# Sch_MB.net
KiCad netlist of a schematic drawn in Altium Designer
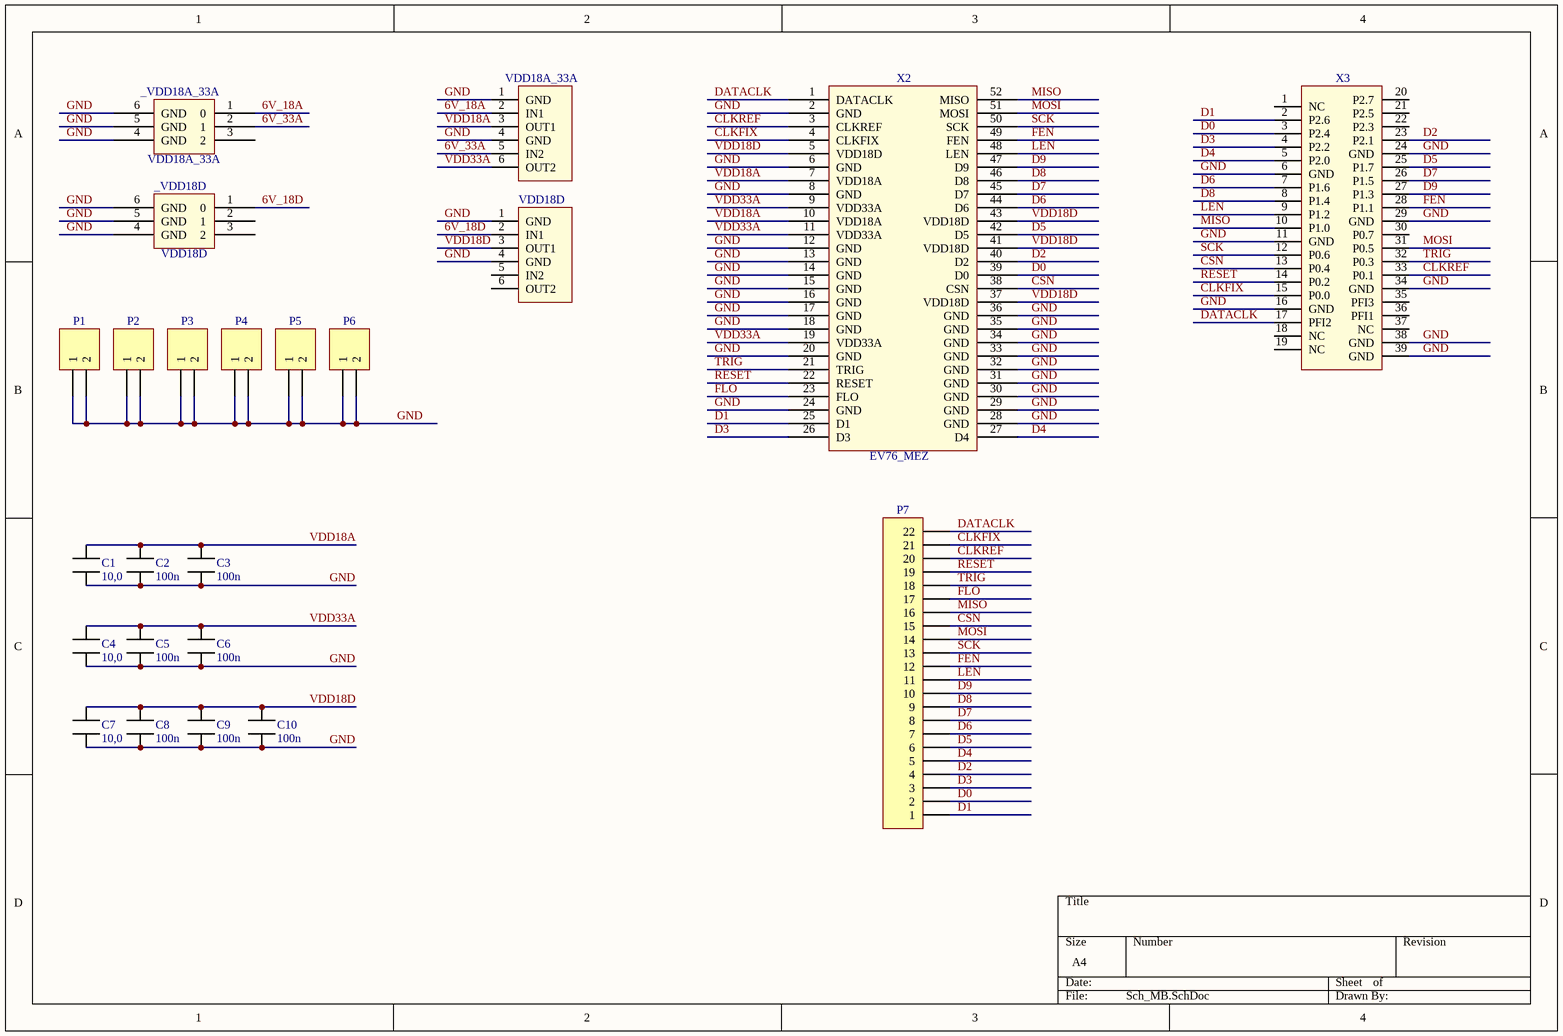
[diagram p0: Sch_MB.SchDoc]

(export (version "E")
  (design (tool "Eeschema 10.0.6"))
  (components
    (comp (ref "C1") (value "10,0") (footprint "Cap_BIG") (libsource (lib "Schlib") (part "CAP_BIG")))
    (comp (ref "C2") (value "100n") (footprint "CAP_SMALL") (libsource (lib "Schlib") (part "CAP_SMALL")))
    (comp (ref "C3") (value "100n") (footprint "CAP_SMALL") (libsource (lib "Schlib") (part "CAP_SMALL")))
    (comp (ref "C4") (value "10,0") (footprint "Cap_BIG") (libsource (lib "Schlib") (part "CAP_BIG")))
    (comp (ref "C5") (value "100n") (footprint "CAP_SMALL") (libsource (lib "Schlib") (part "CAP_SMALL")))
    (comp (ref "C6") (value "100n") (footprint "CAP_SMALL") (libsource (lib "Schlib") (part "CAP_SMALL")))
    (comp (ref "C7") (value "10,0") (footprint "Cap_BIG") (libsource (lib "Schlib") (part "CAP_BIG")))
    (comp (ref "C8") (value "100n") (footprint "CAP_SMALL") (libsource (lib "Schlib") (part "CAP_SMALL")))
    (comp (ref "C9") (value "100n") (footprint "CAP_SMALL") (libsource (lib "Schlib") (part "CAP_SMALL")))
    (comp (ref "C10") (value "100n") (footprint "CAP_SMALL") (libsource (lib "Schlib") (part "CAP_SMALL")))
    (comp (ref "P1")
      (value "Header 2")
      (footprint "HDR1X2")
      (description "Header, 2-Pin")
      (fields (field (name "PUBLISHER") "Altium Limited"))
      (libsource (lib "Miscellaneous Connectors") (part "Header 2"))
    )
    (comp (ref "P2")
      (value "Header 2")
      (footprint "HDR1X2")
      (description "Header, 2-Pin")
      (fields (field (name "PUBLISHER") "Altium Limited"))
      (libsource (lib "Miscellaneous Connectors") (part "Header 2"))
    )
    (comp (ref "P3")
      (value "Header 2")
      (footprint "HDR1X2")
      (description "Header, 2-Pin")
      (fields (field (name "PUBLISHER") "Altium Limited"))
      (libsource (lib "Miscellaneous Connectors") (part "Header 2"))
    )
    (comp (ref "P4")
      (value "Header 2")
      (footprint "HDR1X2")
      (description "Header, 2-Pin")
      (fields (field (name "PUBLISHER") "Altium Limited"))
      (libsource (lib "Miscellaneous Connectors") (part "Header 2"))
    )
    (comp (ref "P5")
      (value "Header 2")
      (footprint "HDR1X2")
      (description "Header, 2-Pin")
      (fields (field (name "PUBLISHER") "Altium Limited"))
      (libsource (lib "Miscellaneous Connectors") (part "Header 2"))
    )
    (comp (ref "P6")
      (value "Header 2")
      (footprint "HDR1X2")
      (description "Header, 2-Pin")
      (fields (field (name "PUBLISHER") "Altium Limited"))
      (libsource (lib "Miscellaneous Connectors") (part "Header 2"))
    )
    (comp (ref "P7")
      (value "Header 22")
      (footprint "HDR1X22")
      (description "Header, 22-Pin")
      (fields (field (name "PUBLISHER") "Altium Limited"))
      (libsource (lib "Miscellaneous Connectors") (part "Header 22"))
    )
    (comp (ref "VDD18A_33A")
      (value "VDD18A_33A")
      (footprint "MEZON_POWER_NEW")
      (libsource (lib "Schlib") (part "MEZON_POWER_NEW"))
    )
    (comp (ref "VDD18D")
      (value "VDD18D")
      (footprint "MEZON_POWER_NEW")
      (libsource (lib "Schlib") (part "MEZON_POWER_NEW"))
    )
    (comp (ref "X2")
      (value "EV76_MEZ")
      (footprint "EV76C661_MEZONINE")
      (libsource (lib "Schlib") (part "EV76C661_MEZ"))
    )
    (comp (ref "X3")
      (value "CHEAP_CON_37_FEMALE")
      (footprint "CHEAP_CONN_FEMALE")
      (libsource (lib "Schlib") (part "CHEAP_CON_37_FEMALE"))
    )
    (comp (ref "_VDD18A_33A")
      (value "VDD18A_33A")
      (footprint "POWER")
      (libsource (lib "Schlib") (part "POWER"))
    )
    (comp (ref "_VDD18D") (value "VDD18D") (footprint "POWER") (libsource (lib "Schlib") (part "POWER")))
  )
  (nets
    (net (code "1") (name "/6V_18A") (class "Default")
      (node (ref "VDD18A_33A") (pin "2") (pinfunction "IN1_2") (pintype "passive"))
      (node (ref "_VDD18A_33A") (pin "1") (pinfunction "0_1") (pintype "passive"))
    )
    (net (code "2") (name "/6V_18D") (class "Default")
      (node (ref "VDD18D") (pin "2") (pinfunction "IN1_2") (pintype "passive"))
      (node (ref "_VDD18D") (pin "1") (pinfunction "0_1") (pintype "passive"))
    )
    (net (code "3") (name "/6V_33A") (class "Default")
      (node (ref "VDD18A_33A") (pin "5") (pinfunction "IN2_5") (pintype "passive"))
      (node (ref "_VDD18A_33A") (pin "2") (pinfunction "1_2") (pintype "passive"))
    )
    (net (code "4") (name "/CLKFIX") (class "Default")
      (node (ref "P7") (pin "21") (pinfunction "21_21") (pintype "passive"))
      (node (ref "X2") (pin "4") (pinfunction "CLKFIX_4") (pintype "passive"))
      (node (ref "X3") (pin "15") (pinfunction "P0.0_15") (pintype "passive"))
    )
    (net (code "5") (name "/CLKREF") (class "Default")
      (node (ref "P7") (pin "20") (pinfunction "20_20") (pintype "passive"))
      (node (ref "X2") (pin "3") (pinfunction "CLKREF_3") (pintype "passive"))
      (node (ref "X3") (pin "33") (pinfunction "P0.1_33") (pintype "passive"))
    )
    (net (code "6") (name "/CSN") (class "Default")
      (node (ref "P7") (pin "15") (pinfunction "15_15") (pintype "passive"))
      (node (ref "X2") (pin "38") (pinfunction "CSN_38") (pintype "passive"))
      (node (ref "X3") (pin "13") (pinfunction "P0.4_13") (pintype "passive"))
    )
    (net (code "7") (name "/D0") (class "Default")
      (node (ref "P7") (pin "2") (pinfunction "2_2") (pintype "passive"))
      (node (ref "X2") (pin "39") (pinfunction "D0_39") (pintype "passive"))
      (node (ref "X3") (pin "3") (pinfunction "P2.4_3") (pintype "passive"))
    )
    (net (code "8") (name "/D1") (class "Default")
      (node (ref "P7") (pin "1") (pinfunction "1_1") (pintype "passive"))
      (node (ref "X2") (pin "25") (pinfunction "D1_25") (pintype "passive"))
      (node (ref "X3") (pin "2") (pinfunction "P2.6_2") (pintype "passive"))
    )
    (net (code "9") (name "/D2") (class "Default")
      (node (ref "P7") (pin "4") (pinfunction "4_4") (pintype "passive"))
      (node (ref "X2") (pin "40") (pinfunction "D2_40") (pintype "passive"))
      (node (ref "X3") (pin "23") (pinfunction "P2.1_23") (pintype "passive"))
    )
    (net (code "10") (name "/D3") (class "Default")
      (node (ref "P7") (pin "3") (pinfunction "3_3") (pintype "passive"))
      (node (ref "X2") (pin "26") (pinfunction "D3_26") (pintype "passive"))
      (node (ref "X3") (pin "4") (pinfunction "P2.2_4") (pintype "passive"))
    )
    (net (code "11") (name "/D4") (class "Default")
      (node (ref "P7") (pin "5") (pinfunction "5_5") (pintype "passive"))
      (node (ref "X2") (pin "27") (pinfunction "D4_27") (pintype "passive"))
      (node (ref "X3") (pin "5") (pinfunction "P2.0_5") (pintype "passive"))
    )
    (net (code "12") (name "/D5") (class "Default")
      (node (ref "P7") (pin "6") (pinfunction "6_6") (pintype "passive"))
      (node (ref "X2") (pin "42") (pinfunction "D5_42") (pintype "passive"))
      (node (ref "X3") (pin "25") (pinfunction "P1.7_25") (pintype "passive"))
    )
    (net (code "13") (name "/D6") (class "Default")
      (node (ref "P7") (pin "7") (pinfunction "7_7") (pintype "passive"))
      (node (ref "X2") (pin "44") (pinfunction "D6_44") (pintype "passive"))
      (node (ref "X3") (pin "7") (pinfunction "P1.6_7") (pintype "passive"))
    )
    (net (code "14") (name "/D7") (class "Default")
      (node (ref "P7") (pin "8") (pinfunction "8_8") (pintype "passive"))
      (node (ref "X2") (pin "45") (pinfunction "D7_45") (pintype "passive"))
      (node (ref "X3") (pin "26") (pinfunction "P1.5_26") (pintype "passive"))
    )
    (net (code "15") (name "/D8") (class "Default")
      (node (ref "P7") (pin "9") (pinfunction "9_9") (pintype "passive"))
      (node (ref "X2") (pin "46") (pinfunction "D8_46") (pintype "passive"))
      (node (ref "X3") (pin "8") (pinfunction "P1.4_8") (pintype "passive"))
    )
    (net (code "16") (name "/D9") (class "Default")
      (node (ref "P7") (pin "10") (pinfunction "10_10") (pintype "passive"))
      (node (ref "X2") (pin "47") (pinfunction "D9_47") (pintype "passive"))
      (node (ref "X3") (pin "27") (pinfunction "P1.3_27") (pintype "passive"))
    )
    (net (code "17") (name "/DATACLK") (class "Default")
      (node (ref "P7") (pin "22") (pinfunction "22_22") (pintype "passive"))
      (node (ref "X2") (pin "1") (pinfunction "DATACLK_1") (pintype "passive"))
      (node (ref "X3") (pin "17") (pinfunction "PFI2_17") (pintype "passive"))
    )
    (net (code "18") (name "/FEN") (class "Default")
      (node (ref "P7") (pin "12") (pinfunction "12_12") (pintype "passive"))
      (node (ref "X2") (pin "49") (pinfunction "FEN_49") (pintype "passive"))
      (node (ref "X3") (pin "28") (pinfunction "P1.1_28") (pintype "passive"))
    )
    (net (code "19") (name "/FLO") (class "Default")
      (node (ref "P7") (pin "17") (pinfunction "17_17") (pintype "passive"))
      (node (ref "X2") (pin "23") (pinfunction "FLO_23") (pintype "passive"))
    )
    (net (code "20") (name "/GND") (class "Default")
      (node (ref "C1") (pin "1") (pinfunction "1_1") (pintype "passive"))
      (node (ref "C10") (pin "1") (pinfunction "1_1") (pintype "passive"))
      (node (ref "C2") (pin "1") (pinfunction "1_1") (pintype "passive"))
      (node (ref "C3") (pin "1") (pinfunction "1_1") (pintype "passive"))
      (node (ref "C4") (pin "1") (pinfunction "1_1") (pintype "passive"))
      (node (ref "C5") (pin "1") (pinfunction "1_1") (pintype "passive"))
      (node (ref "C6") (pin "1") (pinfunction "1_1") (pintype "passive"))
      (node (ref "C7") (pin "1") (pinfunction "1_1") (pintype "passive"))
      (node (ref "C8") (pin "1") (pinfunction "1_1") (pintype "passive"))
      (node (ref "C9") (pin "1") (pinfunction "1_1") (pintype "passive"))
      (node (ref "P1") (pin "1") (pinfunction "1_1") (pintype "passive"))
      (node (ref "P1") (pin "2") (pinfunction "2_2") (pintype "passive"))
      (node (ref "P2") (pin "1") (pinfunction "1_1") (pintype "passive"))
      (node (ref "P2") (pin "2") (pinfunction "2_2") (pintype "passive"))
      (node (ref "P3") (pin "1") (pinfunction "1_1") (pintype "passive"))
      (node (ref "P3") (pin "2") (pinfunction "2_2") (pintype "passive"))
      (node (ref "P4") (pin "1") (pinfunction "1_1") (pintype "passive"))
      (node (ref "P4") (pin "2") (pinfunction "2_2") (pintype "passive"))
      (node (ref "P5") (pin "1") (pinfunction "1_1") (pintype "passive"))
      (node (ref "P5") (pin "2") (pinfunction "2_2") (pintype "passive"))
      (node (ref "P6") (pin "1") (pinfunction "1_1") (pintype "passive"))
      (node (ref "P6") (pin "2") (pinfunction "2_2") (pintype "passive"))
      (node (ref "VDD18A_33A") (pin "1") (pinfunction "GND_1") (pintype "passive"))
      (node (ref "VDD18A_33A") (pin "4") (pinfunction "GND_4") (pintype "passive"))
      (node (ref "VDD18D") (pin "1") (pinfunction "GND_1") (pintype "passive"))
      (node (ref "VDD18D") (pin "4") (pinfunction "GND_4") (pintype "passive"))
      (node (ref "X2") (pin "12") (pinfunction "GND_12") (pintype "passive"))
      (node (ref "X2") (pin "13") (pinfunction "GND_13") (pintype "passive"))
      (node (ref "X2") (pin "14") (pinfunction "GND_14") (pintype "passive"))
      (node (ref "X2") (pin "15") (pinfunction "GND_15") (pintype "passive"))
      (node (ref "X2") (pin "16") (pinfunction "GND_16") (pintype "passive"))
      (node (ref "X2") (pin "17") (pinfunction "GND_17") (pintype "passive"))
      (node (ref "X2") (pin "18") (pinfunction "GND_18") (pintype "passive"))
      (node (ref "X2") (pin "2") (pinfunction "GND_2") (pintype "passive"))
      (node (ref "X2") (pin "20") (pinfunction "GND_20") (pintype "passive"))
      (node (ref "X2") (pin "24") (pinfunction "GND_24") (pintype "passive"))
      (node (ref "X2") (pin "28") (pinfunction "GND_28") (pintype "passive"))
      (node (ref "X2") (pin "29") (pinfunction "GND_29") (pintype "passive"))
      (node (ref "X2") (pin "30") (pinfunction "GND_30") (pintype "passive"))
      (node (ref "X2") (pin "31") (pinfunction "GND_31") (pintype "passive"))
      (node (ref "X2") (pin "32") (pinfunction "GND_32") (pintype "passive"))
      (node (ref "X2") (pin "33") (pinfunction "GND_33") (pintype "passive"))
      (node (ref "X2") (pin "34") (pinfunction "GND_34") (pintype "passive"))
      (node (ref "X2") (pin "35") (pinfunction "GND_35") (pintype "passive"))
      (node (ref "X2") (pin "36") (pinfunction "GND_36") (pintype "passive"))
      (node (ref "X2") (pin "6") (pinfunction "GND_6") (pintype "passive"))
      (node (ref "X2") (pin "8") (pinfunction "GND_8") (pintype "passive"))
      (node (ref "X3") (pin "11") (pinfunction "GND_11") (pintype "passive"))
      (node (ref "X3") (pin "16") (pinfunction "GND_16") (pintype "passive"))
      (node (ref "X3") (pin "24") (pinfunction "GND_24") (pintype "passive"))
      (node (ref "X3") (pin "29") (pinfunction "GND_29") (pintype "passive"))
      (node (ref "X3") (pin "34") (pinfunction "GND_34") (pintype "passive"))
      (node (ref "X3") (pin "38") (pinfunction "GND_38") (pintype "passive"))
      (node (ref "X3") (pin "39") (pinfunction "GND_39") (pintype "passive"))
      (node (ref "X3") (pin "6") (pinfunction "GND_6") (pintype "passive"))
      (node (ref "_VDD18A_33A") (pin "4") (pinfunction "GND_4") (pintype "passive"))
      (node (ref "_VDD18A_33A") (pin "5") (pinfunction "GND_5") (pintype "passive"))
      (node (ref "_VDD18A_33A") (pin "6") (pinfunction "GND_6") (pintype "passive"))
      (node (ref "_VDD18D") (pin "4") (pinfunction "GND_4") (pintype "passive"))
      (node (ref "_VDD18D") (pin "5") (pinfunction "GND_5") (pintype "passive"))
      (node (ref "_VDD18D") (pin "6") (pinfunction "GND_6") (pintype "passive"))
    )
    (net (code "21") (name "/LEN") (class "Default")
      (node (ref "P7") (pin "11") (pinfunction "11_11") (pintype "passive"))
      (node (ref "X2") (pin "48") (pinfunction "LEN_48") (pintype "passive"))
      (node (ref "X3") (pin "9") (pinfunction "P1.2_9") (pintype "passive"))
    )
    (net (code "22") (name "/MISO") (class "Default")
      (node (ref "P7") (pin "16") (pinfunction "16_16") (pintype "passive"))
      (node (ref "X2") (pin "52") (pinfunction "MISO_52") (pintype "passive"))
      (node (ref "X3") (pin "10") (pinfunction "P1.0_10") (pintype "passive"))
    )
    (net (code "23") (name "/MOSI") (class "Default")
      (node (ref "P7") (pin "14") (pinfunction "14_14") (pintype "passive"))
      (node (ref "X2") (pin "51") (pinfunction "MOSI_51") (pintype "passive"))
      (node (ref "X3") (pin "31") (pinfunction "P0.5_31") (pintype "passive"))
    )
    (net (code "24") (name "/RESET") (class "Default")
      (node (ref "P7") (pin "19") (pinfunction "19_19") (pintype "passive"))
      (node (ref "X2") (pin "22") (pinfunction "RESET_22") (pintype "passive"))
      (node (ref "X3") (pin "14") (pinfunction "P0.2_14") (pintype "passive"))
    )
    (net (code "25") (name "/SCK") (class "Default")
      (node (ref "P7") (pin "13") (pinfunction "13_13") (pintype "passive"))
      (node (ref "X2") (pin "50") (pinfunction "SCK_50") (pintype "passive"))
      (node (ref "X3") (pin "12") (pinfunction "P0.6_12") (pintype "passive"))
    )
    (net (code "26") (name "/TRIG") (class "Default")
      (node (ref "P7") (pin "18") (pinfunction "18_18") (pintype "passive"))
      (node (ref "X2") (pin "21") (pinfunction "TRIG_21") (pintype "passive"))
      (node (ref "X3") (pin "32") (pinfunction "P0.3_32") (pintype "passive"))
    )
    (net (code "27") (name "/VDD18A") (class "Default")
      (node (ref "C1") (pin "2") (pinfunction "2_2") (pintype "passive"))
      (node (ref "C2") (pin "2") (pinfunction "2_2") (pintype "passive"))
      (node (ref "C3") (pin "2") (pinfunction "2_2") (pintype "passive"))
      (node (ref "VDD18A_33A") (pin "3") (pinfunction "OUT1_3") (pintype "passive"))
      (node (ref "X2") (pin "10") (pinfunction "VDD18A_10") (pintype "passive"))
      (node (ref "X2") (pin "7") (pinfunction "VDD18A_7") (pintype "passive"))
    )
    (net (code "28") (name "/VDD18D") (class "Default")
      (node (ref "C10") (pin "2") (pinfunction "2_2") (pintype "passive"))
      (node (ref "C7") (pin "2") (pinfunction "2_2") (pintype "passive"))
      (node (ref "C8") (pin "2") (pinfunction "2_2") (pintype "passive"))
      (node (ref "C9") (pin "2") (pinfunction "2_2") (pintype "passive"))
      (node (ref "VDD18D") (pin "3") (pinfunction "OUT1_3") (pintype "passive"))
      (node (ref "X2") (pin "37") (pinfunction "VDD18D_37") (pintype "passive"))
      (node (ref "X2") (pin "41") (pinfunction "VDD18D_41") (pintype "passive"))
      (node (ref "X2") (pin "43") (pinfunction "VDD18D_43") (pintype "passive"))
      (node (ref "X2") (pin "5") (pinfunction "VDD18D_5") (pintype "passive"))
    )
    (net (code "29") (name "/VDD33A") (class "Default")
      (node (ref "C4") (pin "2") (pinfunction "2_2") (pintype "passive"))
      (node (ref "C5") (pin "2") (pinfunction "2_2") (pintype "passive"))
      (node (ref "C6") (pin "2") (pinfunction "2_2") (pintype "passive"))
      (node (ref "VDD18A_33A") (pin "6") (pinfunction "OUT2_6") (pintype "passive"))
      (node (ref "X2") (pin "11") (pinfunction "VDD33A_11") (pintype "passive"))
      (node (ref "X2") (pin "19") (pinfunction "VDD33A_19") (pintype "passive"))
      (node (ref "X2") (pin "9") (pinfunction "VDD33A_9") (pintype "passive"))
    )
    (net (code "30") (name "unconnected-(VDD18D-IN2-Pad5)") (class "Default")
      (node (ref "VDD18D") (pin "5") (pinfunction "IN2_5") (pintype "passive"))
    )
    (net (code "31") (name "unconnected-(VDD18D-OUT2-Pad6)") (class "Default")
      (node (ref "VDD18D") (pin "6") (pinfunction "OUT2_6") (pintype "passive"))
    )
    (net (code "32") (name "unconnected-(X3-NC-Pad1)") (class "Default")
      (node (ref "X3") (pin "1") (pinfunction "NC_1") (pintype "passive"))
    )
    (net (code "33") (name "unconnected-(X3-NC-Pad18)") (class "Default")
      (node (ref "X3") (pin "18") (pinfunction "NC_18") (pintype "passive"))
    )
    (net (code "34") (name "unconnected-(X3-NC-Pad19)") (class "Default")
      (node (ref "X3") (pin "19") (pinfunction "NC_19") (pintype "passive"))
    )
    (net (code "35") (name "unconnected-(X3-NC-Pad37)") (class "Default")
      (node (ref "X3") (pin "37") (pinfunction "NC_37") (pintype "passive"))
    )
    (net (code "36") (name "unconnected-(X3-P0.7-Pad30)") (class "Default")
      (node (ref "X3") (pin "30") (pinfunction "P0.7_30") (pintype "passive"))
    )
    (net (code "37") (name "unconnected-(X3-P2.3-Pad22)") (class "Default")
      (node (ref "X3") (pin "22") (pinfunction "P2.3_22") (pintype "passive"))
    )
    (net (code "38") (name "unconnected-(X3-P2.5-Pad21)") (class "Default")
      (node (ref "X3") (pin "21") (pinfunction "P2.5_21") (pintype "passive"))
    )
    (net (code "39") (name "unconnected-(X3-P2.7-Pad20)") (class "Default")
      (node (ref "X3") (pin "20") (pinfunction "P2.7_20") (pintype "passive"))
    )
    (net (code "40") (name "unconnected-(X3-PFI1-Pad36)") (class "Default")
      (node (ref "X3") (pin "36") (pinfunction "PFI1_36") (pintype "passive"))
    )
    (net (code "41") (name "unconnected-(X3-PFI3-Pad35)") (class "Default")
      (node (ref "X3") (pin "35") (pinfunction "PFI3_35") (pintype "passive"))
    )
    (net (code "42") (name "unconnected-(_VDD18A_33A-2-Pad3)") (class "Default")
      (node (ref "_VDD18A_33A") (pin "3") (pinfunction "2_3") (pintype "passive"))
    )
    (net (code "43") (name "unconnected-(_VDD18D-1-Pad2)") (class "Default")
      (node (ref "_VDD18D") (pin "2") (pinfunction "1_2") (pintype "passive"))
    )
    (net (code "44") (name "unconnected-(_VDD18D-2-Pad3)") (class "Default")
      (node (ref "_VDD18D") (pin "3") (pinfunction "2_3") (pintype "passive"))
    )
  )
)
